# Board_V1_0.net
KiCad netlist of a schematic drawn in Altium Designer
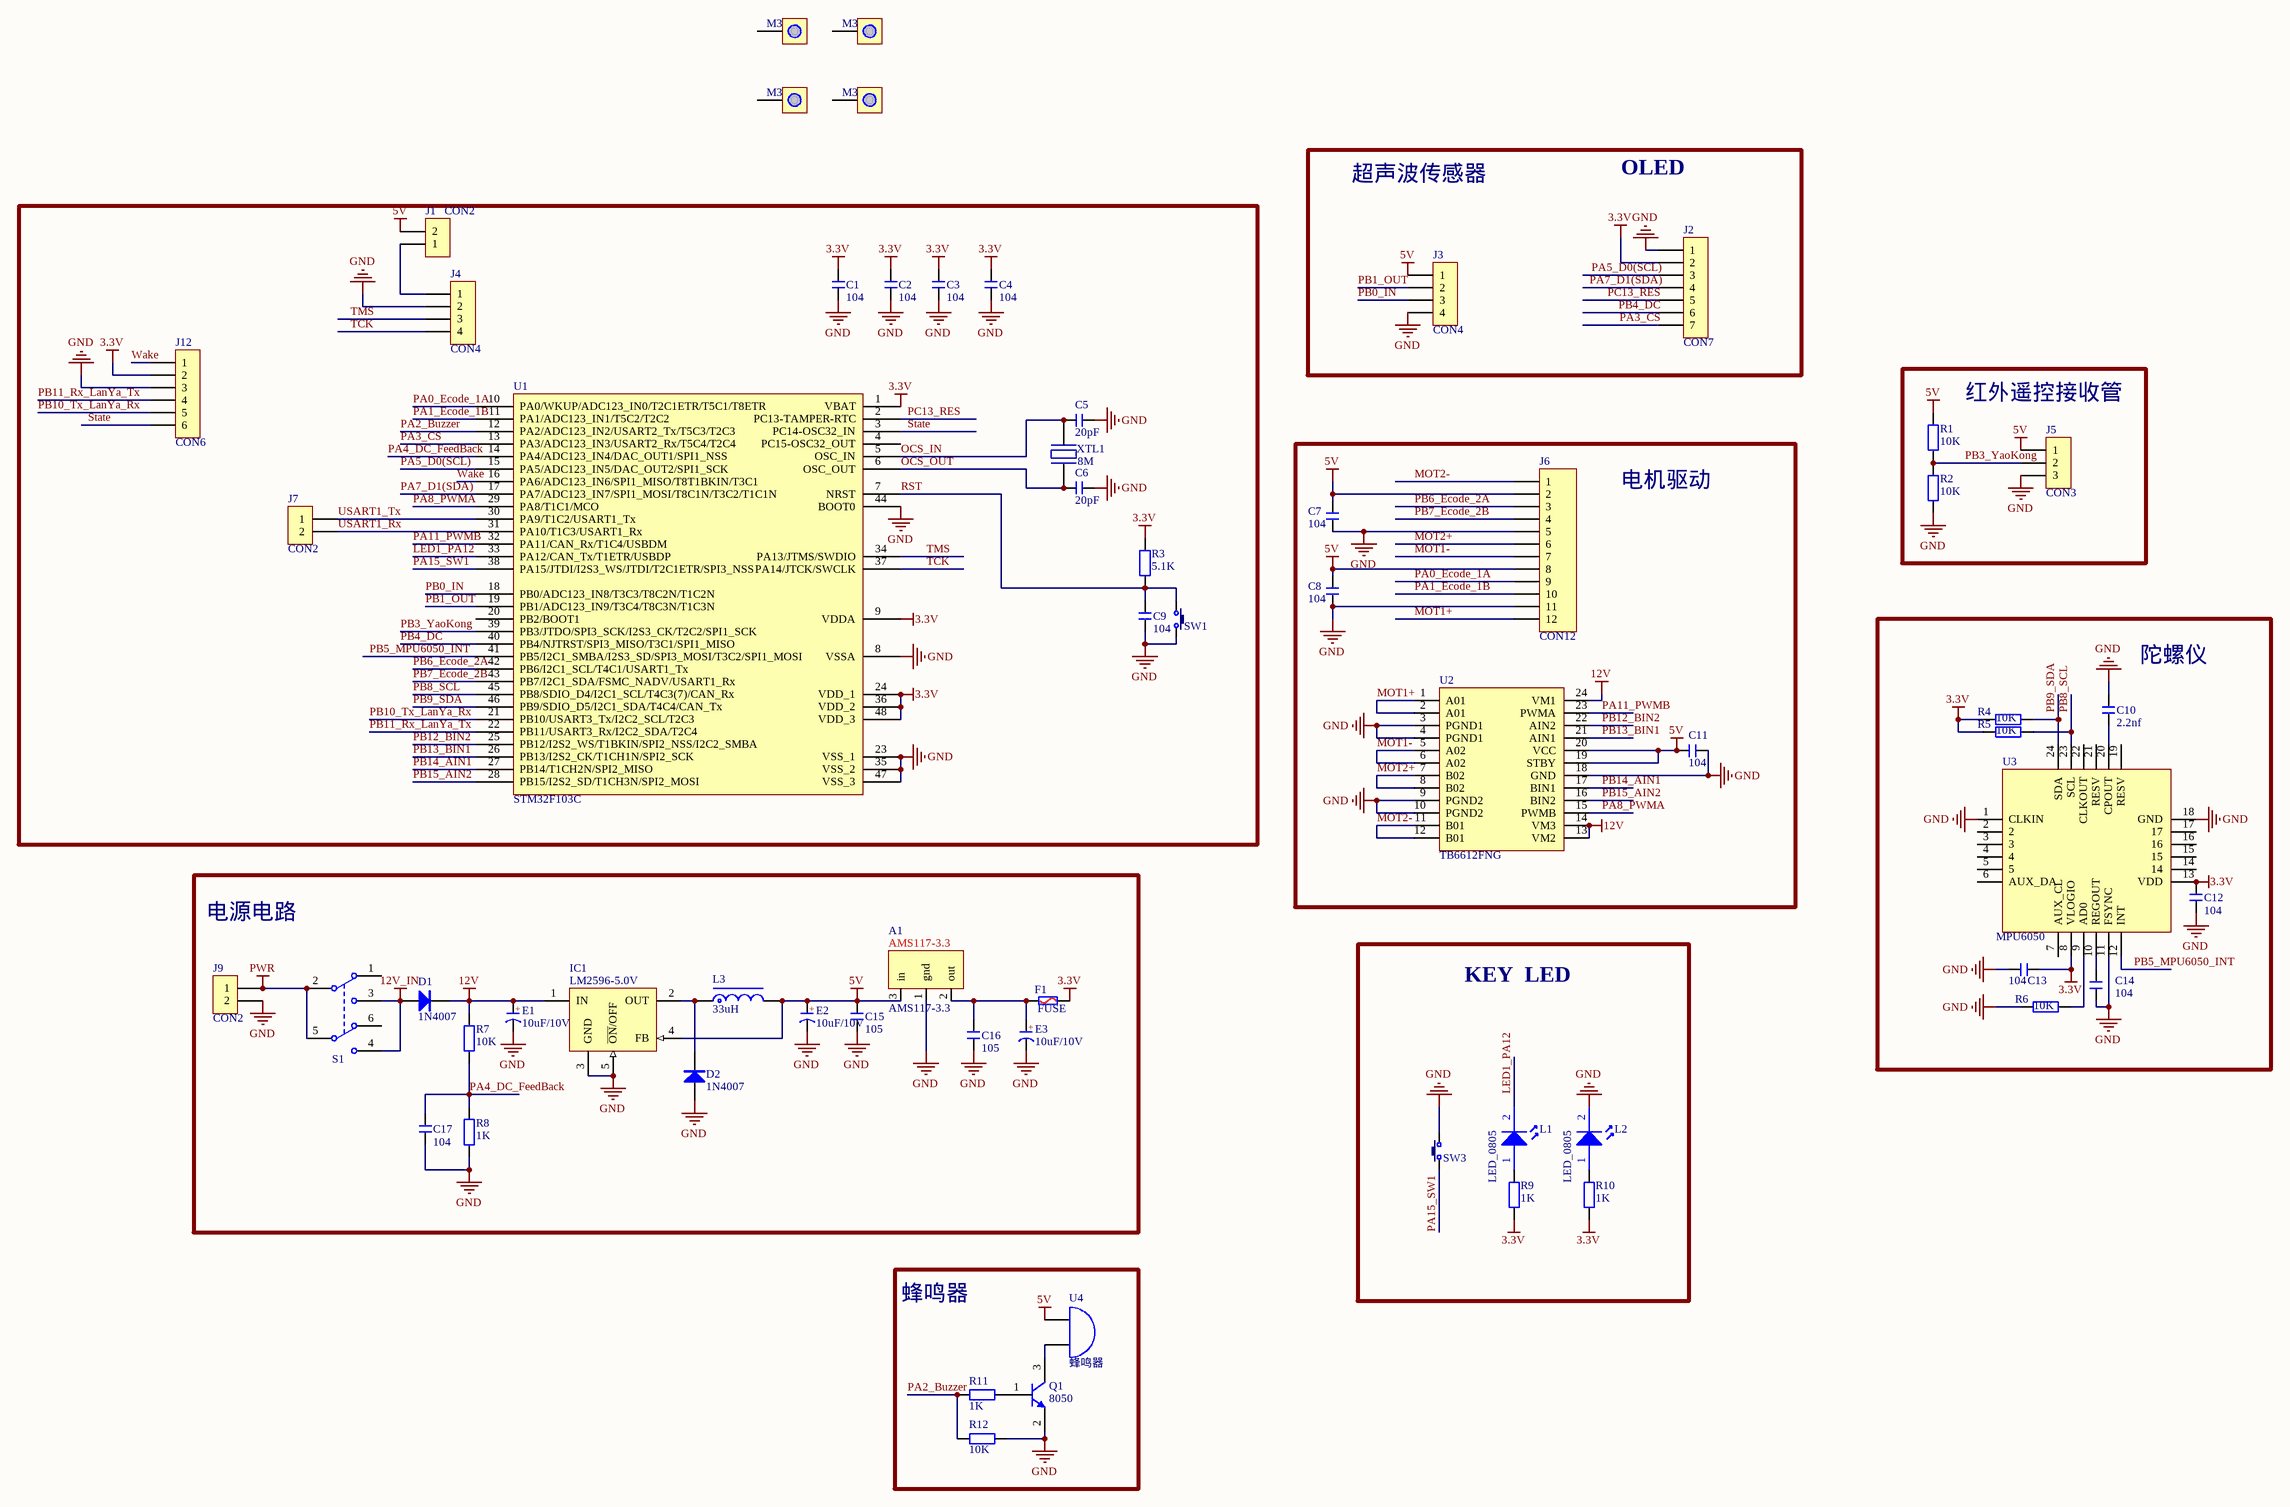
[diagram p0: 平衡车Board_V1.0.SchDoc]

(export (version "E")
  (design (tool "Eeschema 10.0.6"))
  (components
    (comp (ref "A1") (value "AMS117-3.3") (footprint "SOT223_N") (libsource (lib "MP3") (part "AMS117-3.3")))
    (comp (ref "C1")
      (value "104")
      (footprint "C 0603_M")
      (description "无极性贴片电容")
      (libsource (lib "3.1   - 电阻-电容-电感") (part "C"))
    )
    (comp (ref "C2")
      (value "104")
      (footprint "C 0603_M")
      (description "无极性贴片电容")
      (libsource (lib "3.1   - 电阻-电容-电感") (part "C"))
    )
    (comp (ref "C3")
      (value "104")
      (footprint "C 0603_M")
      (description "无极性贴片电容")
      (libsource (lib "3.1   - 电阻-电容-电感") (part "C"))
    )
    (comp (ref "C4")
      (value "104")
      (footprint "C 0603_M")
      (description "无极性贴片电容")
      (libsource (lib "3.1   - 电阻-电容-电感") (part "C"))
    )
    (comp (ref "C5")
      (value "20pF")
      (footprint "C 0603_M")
      (description "无极性贴片电容")
      (libsource (lib "3.1   - 电阻-电容-电感") (part "C"))
    )
    (comp (ref "C6")
      (value "20pF")
      (footprint "C 0603_M")
      (description "无极性贴片电容")
      (libsource (lib "3.1   - 电阻-电容-电感") (part "C"))
    )
    (comp (ref "C7")
      (value "104")
      (footprint "C 0603_M")
      (description "无极性贴片电容")
      (libsource (lib "3.1   - 电阻-电容-电感") (part "C"))
    )
    (comp (ref "C8")
      (value "104")
      (footprint "C 0603_M")
      (description "无极性贴片电容")
      (libsource (lib "3.1   - 电阻-电容-电感") (part "C"))
    )
    (comp (ref "C9")
      (value "104")
      (footprint "C 0603_M")
      (description "无极性贴片电容")
      (libsource (lib "3.1   - 电阻-电容-电感") (part "C"))
    )
    (comp (ref "C10")
      (value "2.2nf")
      (footprint "C 0603_M")
      (description "无极性贴片电容")
      (libsource (lib "3.1   - 电阻-电容-电感") (part "C"))
    )
    (comp (ref "C11")
      (value "104")
      (footprint "C 0603_M")
      (description "无极性贴片电容")
      (libsource (lib "3.1   - 电阻-电容-电感") (part "C"))
    )
    (comp (ref "C12")
      (value "104")
      (footprint "C 0603_M")
      (description "无极性贴片电容")
      (libsource (lib "3.1   - 电阻-电容-电感") (part "C"))
    )
    (comp (ref "C13")
      (value "104")
      (footprint "C 0603_M")
      (description "无极性贴片电容")
      (libsource (lib "3.1   - 电阻-电容-电感") (part "C"))
    )
    (comp (ref "C14")
      (value "104")
      (footprint "C 0603_M")
      (description "无极性贴片电容")
      (libsource (lib "3.1   - 电阻-电容-电感") (part "C"))
    )
    (comp (ref "C15")
      (value "105")
      (footprint "C 0805_M")
      (description "无极性贴片电容")
      (libsource (lib "3.1   - 电阻-电容-电感") (part "C"))
    )
    (comp (ref "C16")
      (value "105")
      (footprint "C 0805_M")
      (description "无极性贴片电容")
      (libsource (lib "3.1   - 电阻-电容-电感") (part "C"))
    )
    (comp (ref "C17")
      (value "104")
      (footprint "C 0603_M")
      (description "无极性贴片电容")
      (libsource (lib "3.1   - 电阻-电容-电感") (part "C"))
    )
    (comp (ref "D1")
      (value "1N4007")
      (footprint "DO-41")
      (description "整流二极管")
      (libsource (lib "8.1   - 二极管-整流桥") (part "1N4007"))
    )
    (comp (ref "D2")
      (value "1N4007")
      (footprint "DO-41")
      (description "整流二极管")
      (libsource (lib "8.1   - 二极管-整流桥") (part "1N4007"))
    )
    (comp (ref "E1")
      (value "10uF/10V")
      (footprint "CM D(6.3*7.7)")
      (description "贴片电解电容")
      (libsource (lib "3.1   - 电阻-电容-电感") (part "C-CM"))
    )
    (comp (ref "E2")
      (value "10uF/10V")
      (footprint "CM D(6.3*7.7)")
      (description "贴片电解电容")
      (libsource (lib "3.1   - 电阻-电容-电感") (part "C-CM"))
    )
    (comp (ref "E3")
      (value "10uF/10V")
      (footprint "CM D(6.3*7.7)")
      (description "贴片电解电容")
      (libsource (lib "3.1   - 电阻-电容-电感") (part "C-CM"))
    )
    (comp (ref "F1") (value "FUSE") (footprint "FU 1206") (libsource (lib "MP3") (part "FUSE")))
    (comp (ref "IC1")
      (value "LM2596-5.0V")
      (footprint "TO263-5A")
      (description "DC降压芯片")
      (libsource (lib "1.3   - 电源类芯片") (part "LM2596-5.0"))
    )
    (comp (ref "J1")
      (value "CON2")
      (footprint "HDR2.54-LI-2P")
      (description "Connector")
      (libsource (lib "") (part "CON2_1"))
    )
    (comp (ref "J2")
      (value "CON7")
      (footprint "HDR2.54-M-LI-7P - for-Oled")
      (description "Connector")
      (libsource (lib "4.16 - 插件") (part "CON7"))
    )
    (comp (ref "J3")
      (value "CON4")
      (footprint "HDR2.54-M-LI-4P")
      (description "Connector")
      (libsource (lib "4.16 - 插件") (part "CON4"))
    )
    (comp (ref "J4")
      (value "CON4")
      (footprint "HDR2.54-WI-4P")
      (description "Connector")
      (libsource (lib "4.16 - 插件") (part "CON4"))
    )
    (comp (ref "J5")
      (value "CON3")
      (footprint "TO92A - duplicate")
      (description "Connector")
      (libsource (lib "4.16 - 插件") (part "CON3"))
    )
    (comp (ref "J6")
      (value "CON12")
      (footprint "XH2.54-LI-12P")
      (description "Connector")
      (libsource (lib "4.16 - 插件") (part "CON12"))
    )
    (comp (ref "J7")
      (value "CON2")
      (footprint "HDR2.54-LI-2P")
      (description "Connector")
      (libsource (lib "4.16 - 插件") (part "CON2"))
    )
    (comp (ref "J9")
      (value "CON2")
      (footprint "CZ-5.08-L-Z-2P")
      (description "Connector")
      (libsource (lib "4.16 - 插件") (part "CON2"))
    )
    (comp (ref "J12")
      (value "CON6")
      (footprint "HDR2.54-M-LI-6P - for-wifi")
      (description "Connector")
      (libsource (lib "4.16 - 插件") (part "CON6"))
    )
    (comp (ref "L1") (value "LED_0805") (footprint "LED 0805G") (libsource (lib "MP3") (part "LED_0805")))
    (comp (ref "L2") (value "LED_0805") (footprint "LED 0805G") (libsource (lib "MP3") (part "LED_0805")))
    (comp (ref "L3")
      (value "33uH")
      (footprint "NR3012")
      (description "NR磁胶电感")
      (libsource (lib "3.1   - 电阻-电容-电感") (part "L-NR"))
    )
    (comp (ref "M3") (value "M3") (footprint "M3x20_L") (libsource (lib "MP3") (part "M3")))
    (comp (ref "M4") (value "M3") (footprint "M3x20_L") (libsource (lib "MP3") (part "M3")))
    (comp (ref "M5") (value "M3") (footprint "M3x20_L") (libsource (lib "MP3") (part "M3")))
    (comp (ref "M6") (value "M3") (footprint "M3x20_L") (libsource (lib "MP3") (part "M3")))
    (comp (ref "Q1") (value "8050") (footprint "SOT23-3M") (libsource (lib "PCB_M") (part "NPN")))
    (comp (ref "R1")
      (value "10K")
      (footprint "R 0603_M")
      (description "贴片电阻")
      (libsource (lib "3.1   - 电阻-电容-电感") (part "R"))
    )
    (comp (ref "R2")
      (value "10K")
      (footprint "R 0603_M")
      (description "贴片电阻")
      (libsource (lib "3.1   - 电阻-电容-电感") (part "R"))
    )
    (comp (ref "R3")
      (value "5.1K")
      (footprint "R 0603_M")
      (description "贴片电阻")
      (libsource (lib "3.1   - 电阻-电容-电感") (part "R"))
    )
    (comp (ref "R4")
      (value "10K")
      (footprint "R 0603_M")
      (description "贴片电阻")
      (libsource (lib "3.1   - 电阻-电容-电感") (part "R"))
    )
    (comp (ref "R5")
      (value "10K")
      (footprint "R 0603_M")
      (description "贴片电阻")
      (libsource (lib "3.1   - 电阻-电容-电感") (part "R"))
    )
    (comp (ref "R6")
      (value "10K")
      (footprint "R 0603_M")
      (description "贴片电阻")
      (libsource (lib "3.1   - 电阻-电容-电感") (part "R"))
    )
    (comp (ref "R7")
      (value "10K")
      (footprint "R 0603_M")
      (description "贴片电阻")
      (libsource (lib "3.1   - 电阻-电容-电感") (part "R"))
    )
    (comp (ref "R8")
      (value "1K")
      (footprint "R 0603_M")
      (description "贴片电阻")
      (libsource (lib "3.1   - 电阻-电容-电感") (part "R"))
    )
    (comp (ref "R9")
      (value "1K")
      (footprint "R 0603_M")
      (description "贴片电阻")
      (libsource (lib "3.1   - 电阻-电容-电感") (part "R"))
    )
    (comp (ref "R10")
      (value "1K")
      (footprint "R 0603_M")
      (description "贴片电阻")
      (libsource (lib "3.1   - 电阻-电容-电感") (part "R"))
    )
    (comp (ref "R11")
      (value "1K")
      (footprint "R 0603_M")
      (description "贴片电阻")
      (libsource (lib "3.1   - 电阻-电容-电感") (part "R"))
    )
    (comp (ref "R12")
      (value "10K")
      (footprint "R 0603_M")
      (description "贴片电阻")
      (libsource (lib "3.1   - 电阻-电容-电感") (part "R"))
    )
    (comp (ref "S1")
      (value "SK-22D02")
      (footprint "SK-22D02")
      (description "2路波动开关")
      (libsource (lib "5.1   - 按键-开关") (part "SSW-2P"))
    )
    (comp (ref "SW1")
      (value "3x6x5")
      (footprint "TSW DIP-6*6*5")
      (description "3x6轻触开关")
      (libsource (lib "5.1   - 按键-开关") (part "TSW 3x6"))
    )
    (comp (ref "SW3")
      (value "3x6x5")
      (footprint "TSW DIP-6*6*5")
      (description "3x6轻触开关")
      (libsource (lib "") (part "TSW 3x6_1"))
    )
    (comp (ref "U1")
      (value "STM32F103C")
      (footprint "LQFP48 7X7_M")
      (description "STM32单片机48引脚")
      (libsource (lib "2.3.8 - STM32芯片") (part "STM32F103C"))
    )
    (comp (ref "U2")
      (value "TB6612FNG")
      (footprint "SSOP24_M")
      (description "直流电机驱动芯片")
      (libsource (lib "MP3") (part "TB6612FNG"))
    )
    (comp (ref "U3")
      (value "MPU6050")
      (footprint "QFN24 4x4_M")
      (description "陀螺仪")
      (libsource (lib "MP3") (part "MPU6050"))
    )
    (comp (ref "U4")
      (value "蜂鸣器")
      (footprint "BEEP 5x9x5.5")
      (description "Bell")
      (libsource (lib "9.2.1 - 声亮元件") (part "蜂鸣器"))
    )
    (comp (ref "XTL1") (value "8M") (footprint "OSC HC-49S") (libsource (lib "MP3") (part "XTL")))
  )
  (nets
    (net (code "1") (name "/LED1_PA12") (class "Default")
      (node (ref "L1") (pin "2") (pinfunction "2_2") (pintype "passive"))
      (node (ref "U1") (pin "33") (pinfunction "PA12/CAN_Tx/T1ETR/USBDP_33") (pintype "passive"))
    )
    (net (code "2") (name "/MOT1+") (class "Default")
      (node (ref "J6") (pin "12") (pinfunction "12_12") (pintype "passive"))
      (node (ref "U2") (pin "1") (pinfunction "A01_1") (pintype "passive"))
      (node (ref "U2") (pin "2") (pinfunction "A01_2") (pintype "passive"))
    )
    (net (code "3") (name "/MOT1-") (class "Default")
      (node (ref "J6") (pin "7") (pinfunction "7_7") (pintype "passive"))
      (node (ref "U2") (pin "5") (pinfunction "A02_5") (pintype "passive"))
      (node (ref "U2") (pin "6") (pinfunction "A02_6") (pintype "passive"))
    )
    (net (code "4") (name "/MOT2+") (class "Default")
      (node (ref "J6") (pin "6") (pinfunction "6_6") (pintype "passive"))
      (node (ref "U2") (pin "7") (pinfunction "B02_7") (pintype "passive"))
      (node (ref "U2") (pin "8") (pinfunction "B02_8") (pintype "passive"))
    )
    (net (code "5") (name "/MOT2-") (class "Default")
      (node (ref "J6") (pin "1") (pinfunction "1_1") (pintype "passive"))
      (node (ref "U2") (pin "11") (pinfunction "B01_11") (pintype "passive"))
      (node (ref "U2") (pin "12") (pinfunction "B01_12") (pintype "passive"))
    )
    (net (code "6") (name "/OCS_IN") (class "Default")
      (node (ref "C5") (pin "2") (pinfunction "2_2") (pintype "passive"))
      (node (ref "U1") (pin "5") (pinfunction "OSC_IN_5") (pintype "passive"))
      (node (ref "XTL1") (pin "2") (pinfunction "2_2") (pintype "passive"))
    )
    (net (code "7") (name "/OCS_OUT") (class "Default")
      (node (ref "C6") (pin "2") (pinfunction "2_2") (pintype "passive"))
      (node (ref "U1") (pin "6") (pinfunction "OSC_OUT_6") (pintype "passive"))
      (node (ref "XTL1") (pin "1") (pinfunction "1_1") (pintype "passive"))
    )
    (net (code "8") (name "/PA0_Ecode_1A") (class "Default")
      (node (ref "J6") (pin "9") (pinfunction "9_9") (pintype "passive"))
      (node (ref "U1") (pin "10") (pinfunction "PA0/WKUP/ADC123_IN0/T2C1ETR/T5C1/T8ETR_10") (pintype "passive"))
    )
    (net (code "9") (name "/PA1_Ecode_1B") (class "Default")
      (node (ref "J6") (pin "10") (pinfunction "10_10") (pintype "passive"))
      (node (ref "U1") (pin "11") (pinfunction "PA1/ADC123_IN1/T5C2/T2C2_11") (pintype "passive"))
    )
    (net (code "10") (name "/PA2_Buzzer") (class "Default")
      (node (ref "R11") (pin "2") (pinfunction "2_2") (pintype "passive"))
      (node (ref "R12") (pin "2") (pinfunction "2_2") (pintype "passive"))
      (node (ref "U1") (pin "12") (pinfunction "PA2/ADC123_IN2/USART2_Tx/T5C3/T2C3_12") (pintype "passive"))
    )
    (net (code "11") (name "/PA3_CS") (class "Default")
      (node (ref "J2") (pin "7") (pinfunction "7_7") (pintype "passive"))
      (node (ref "U1") (pin "13") (pinfunction "PA3/ADC123_IN3/USART2_Rx/T5C4/T2C4_13") (pintype "passive"))
    )
    (net (code "12") (name "/PA4_DC_FeedBack") (class "Default")
      (node (ref "C17") (pin "2") (pinfunction "2_2") (pintype "passive"))
      (node (ref "R7") (pin "1") (pinfunction "1_1") (pintype "passive"))
      (node (ref "R8") (pin "2") (pinfunction "2_2") (pintype "passive"))
      (node (ref "U1") (pin "14") (pinfunction "PA4/ADC123_IN4/DAC_OUT1/SPI1_NSS_14") (pintype "passive"))
    )
    (net (code "13") (name "/PA5_D0(SCL)") (class "Default")
      (node (ref "J2") (pin "3") (pinfunction "3_3") (pintype "passive"))
      (node (ref "U1") (pin "15") (pinfunction "PA5/ADC123_IN5/DAC_OUT2/SPI1_SCK_15") (pintype "passive"))
    )
    (net (code "14") (name "/PA7_D1(SDA)") (class "Default")
      (node (ref "J2") (pin "4") (pinfunction "4_4") (pintype "passive"))
      (node (ref "U1") (pin "17") (pinfunction "PA7/ADC123_IN7/SPI1_MOSI/T8C1N/T3C2/T1C1N_17") (pintype "passive"))
    )
    (net (code "15") (name "/PA8_PWMA") (class "Default")
      (node (ref "U1") (pin "29") (pinfunction "PA8/T1C1/MCO_29") (pintype "passive"))
      (node (ref "U2") (pin "15") (pinfunction "PWMB_15") (pintype "passive"))
    )
    (net (code "16") (name "/PA11_PWMB") (class "Default")
      (node (ref "U1") (pin "32") (pinfunction "PA11/CAN_Rx/T1C4/USBDM_32") (pintype "passive"))
      (node (ref "U2") (pin "23") (pinfunction "PWMA_23") (pintype "passive"))
    )
    (net (code "17") (name "/PA15_SW1") (class "Default")
      (node (ref "SW3") (pin "1") (pinfunction "1_1") (pintype "passive"))
      (node (ref "U1") (pin "38") (pinfunction "PA15/JTDI/I2S3_WS/JTDI/T2C1ETR/SPI3_NSS_38") (pintype "passive"))
    )
    (net (code "18") (name "/PB0_IN") (class "Default")
      (node (ref "J3") (pin "3") (pinfunction "3_3") (pintype "passive"))
      (node (ref "U1") (pin "18") (pinfunction "PB0/ADC123_IN8/T3C3/T8C2N/T1C2N_18") (pintype "passive"))
    )
    (net (code "19") (name "/PB1_OUT") (class "Default")
      (node (ref "J3") (pin "2") (pinfunction "2_2") (pintype "passive"))
      (node (ref "U1") (pin "19") (pinfunction "PB1/ADC123_IN9/T3C4/T8C3N/T1C3N_19") (pintype "passive"))
    )
    (net (code "20") (name "/PB3_YaoKong") (class "Default")
      (node (ref "J5") (pin "2") (pinfunction "2_2") (pintype "passive"))
      (node (ref "R1") (pin "1") (pinfunction "1_1") (pintype "passive"))
      (node (ref "R2") (pin "1") (pinfunction "1_1") (pintype "passive"))
      (node (ref "U1") (pin "39") (pinfunction "PB3/JTDO/SPI3_SCK/I2S3_CK/T2C2/SPI1_SCK_39") (pintype "passive"))
    )
    (net (code "21") (name "/PB4_DC") (class "Default")
      (node (ref "J2") (pin "6") (pinfunction "6_6") (pintype "passive"))
      (node (ref "U1") (pin "40") (pinfunction "PB4/NJTRST/SPI3_MISO/T3C1/SPI1_MISO_40") (pintype "passive"))
    )
    (net (code "22") (name "/PB5_MPU6050_INT") (class "Default")
      (node (ref "U1") (pin "41") (pinfunction "PB5/I2C1_SMBA/I2S3_SD/SPI3_MOSI/T3C2/SPI1_MOSI_41") (pintype "passive"))
      (node (ref "U3") (pin "12") (pinfunction "INT_12") (pintype "passive"))
    )
    (net (code "23") (name "/PB6_Ecode_2A") (class "Default")
      (node (ref "J6") (pin "3") (pinfunction "3_3") (pintype "passive"))
      (node (ref "U1") (pin "42") (pinfunction "PB6/I2C1_SCL/T4C1/USART1_Tx_42") (pintype "passive"))
    )
    (net (code "24") (name "/PB7_Ecode_2B") (class "Default")
      (node (ref "J6") (pin "4") (pinfunction "4_4") (pintype "passive"))
      (node (ref "U1") (pin "43") (pinfunction "PB7/I2C1_SDA/FSMC_NADV/USART1_Rx_43") (pintype "passive"))
    )
    (net (code "25") (name "/PB8_SCL") (class "Default")
      (node (ref "R5") (pin "1") (pinfunction "1_1") (pintype "passive"))
      (node (ref "U1") (pin "45") (pinfunction "PB8/SDIO_D4/I2C1_SCL/T4C3(7)/CAN_Rx_45") (pintype "passive"))
      (node (ref "U3") (pin "23") (pinfunction "SCL_23") (pintype "passive"))
    )
    (net (code "26") (name "/PB9_SDA") (class "Default")
      (node (ref "R4") (pin "1") (pinfunction "1_1") (pintype "passive"))
      (node (ref "U1") (pin "46") (pinfunction "PB9/SDIO_D5/I2C1_SDA/T4C4/CAN_Tx_46") (pintype "passive"))
      (node (ref "U3") (pin "24") (pinfunction "SDA_24") (pintype "passive"))
    )
    (net (code "27") (name "/PB10_Tx_LanYa_Rx") (class "Default")
      (node (ref "J12") (pin "5") (pinfunction "5_5") (pintype "passive"))
      (node (ref "U1") (pin "21") (pinfunction "PB10/USART3_Tx/I2C2_SCL/T2C3_21") (pintype "passive"))
    )
    (net (code "28") (name "/PB11_Rx_LanYa_Tx") (class "Default")
      (node (ref "J12") (pin "4") (pinfunction "4_4") (pintype "passive"))
      (node (ref "U1") (pin "22") (pinfunction "PB11/USART3_Rx/I2C2_SDA/T2C4_22") (pintype "passive"))
    )
    (net (code "29") (name "/PB12_BIN2") (class "Default")
      (node (ref "U1") (pin "25") (pinfunction "PB12/I2S2_WS/T1BKIN/SPI2_NSS/I2C2_SMBA_25") (pintype "passive"))
      (node (ref "U2") (pin "22") (pinfunction "AIN2_22") (pintype "passive"))
    )
    (net (code "30") (name "/PB13_BIN1") (class "Default")
      (node (ref "U1") (pin "26") (pinfunction "PB13/I2S2_CK/T1CH1N/SPI2_SCK_26") (pintype "passive"))
      (node (ref "U2") (pin "21") (pinfunction "AIN1_21") (pintype "passive"))
    )
    (net (code "31") (name "/PB14_AIN1") (class "Default")
      (node (ref "U1") (pin "27") (pinfunction "PB14/T1CH2N/SPI2_MISO_27") (pintype "passive"))
      (node (ref "U2") (pin "17") (pinfunction "BIN1_17") (pintype "passive"))
    )
    (net (code "32") (name "/PB15_AIN2") (class "Default")
      (node (ref "U1") (pin "28") (pinfunction "PB15/I2S2_SD/T1CH3N/SPI2_MOSI_28") (pintype "passive"))
      (node (ref "U2") (pin "16") (pinfunction "BIN2_16") (pintype "passive"))
    )
    (net (code "33") (name "/PC13_RES") (class "Default")
      (node (ref "J2") (pin "5") (pinfunction "5_5") (pintype "passive"))
      (node (ref "U1") (pin "2") (pinfunction "PC13-TAMPER-RTC_2") (pintype "passive"))
    )
    (net (code "34") (name "/RST") (class "Default")
      (node (ref "C9") (pin "2") (pinfunction "2_2") (pintype "passive"))
      (node (ref "R3") (pin "1") (pinfunction "1_1") (pintype "passive"))
      (node (ref "SW1") (pin "1") (pinfunction "1_1") (pintype "passive"))
      (node (ref "U1") (pin "7") (pinfunction "NRST_7") (pintype "passive"))
    )
    (net (code "35") (name "/State") (class "Default")
      (node (ref "J12") (pin "6") (pinfunction "6_6") (pintype "passive"))
      (node (ref "U1") (pin "3") (pinfunction "PC14-OSC32_IN_3") (pintype "passive"))
    )
    (net (code "36") (name "/TCK") (class "Default")
      (node (ref "J4") (pin "4") (pinfunction "4_4") (pintype "passive"))
      (node (ref "U1") (pin "37") (pinfunction "PA14/JTCK/SWCLK_37") (pintype "passive"))
    )
    (net (code "37") (name "/TMS") (class "Default")
      (node (ref "J4") (pin "3") (pinfunction "3_3") (pintype "passive"))
      (node (ref "U1") (pin "34") (pinfunction "PA13/JTMS/SWDIO_34") (pintype "passive"))
    )
    (net (code "38") (name "/USART1_Rx") (class "Default")
      (node (ref "J7") (pin "2") (pinfunction "2_2") (pintype "passive"))
      (node (ref "U1") (pin "31") (pinfunction "PA10/T1C3/USART1_Rx_31") (pintype "passive"))
    )
    (net (code "39") (name "/USART1_Tx") (class "Default")
      (node (ref "J7") (pin "1") (pinfunction "1_1") (pintype "passive"))
      (node (ref "U1") (pin "30") (pinfunction "PA9/T1C2/USART1_Tx_30") (pintype "passive"))
    )
    (net (code "40") (name "/Wake") (class "Default")
      (node (ref "J12") (pin "1") (pinfunction "1_1") (pintype "passive"))
      (node (ref "U1") (pin "16") (pinfunction "PA6/ADC123_IN6/SPI1_MISO/T8T1BKIN/T3C1_16") (pintype "passive"))
    )
    (net (code "41") (name "3.3V") (class "Default")
      (node (ref "C1") (pin "2") (pinfunction "2_2") (pintype "passive"))
      (node (ref "C12") (pin "2") (pinfunction "2_2") (pintype "passive"))
      (node (ref "C13") (pin "1") (pinfunction "1_1") (pintype "passive"))
      (node (ref "C2") (pin "2") (pinfunction "2_2") (pintype "passive"))
      (node (ref "C3") (pin "2") (pinfunction "2_2") (pintype "passive"))
      (node (ref "C4") (pin "2") (pinfunction "2_2") (pintype "passive"))
      (node (ref "F1") (pin "1") (pinfunction "1_1") (pintype "passive"))
      (node (ref "J12") (pin "2") (pinfunction "2_2") (pintype "passive"))
      (node (ref "J2") (pin "2") (pinfunction "2_2") (pintype "passive"))
      (node (ref "R10") (pin "1") (pinfunction "1_1") (pintype "passive"))
      (node (ref "R3") (pin "2") (pinfunction "2_2") (pintype "passive"))
      (node (ref "R4") (pin "2") (pinfunction "2_2") (pintype "passive"))
      (node (ref "R5") (pin "2") (pinfunction "2_2") (pintype "passive"))
      (node (ref "R9") (pin "1") (pinfunction "1_1") (pintype "passive"))
      (node (ref "U1") (pin "1") (pinfunction "VBAT_1") (pintype "passive"))
      (node (ref "U1") (pin "24") (pinfunction "VDD_1_24") (pintype "passive"))
      (node (ref "U1") (pin "36") (pinfunction "VDD_2_36") (pintype "passive"))
      (node (ref "U1") (pin "48") (pinfunction "VDD_3_48") (pintype "passive"))
      (node (ref "U1") (pin "9") (pinfunction "VDDA_9") (pintype "passive"))
      (node (ref "U3") (pin "13") (pinfunction "VDD_13") (pintype "passive"))
      (node (ref "U3") (pin "8") (pinfunction "VLOGIO_8") (pintype "passive"))
    )
    (net (code "42") (name "5V") (class "Default")
      (node (ref "A1") (pin "3") (pinfunction "in_3") (pintype "passive"))
      (node (ref "C11") (pin "2") (pinfunction "2_2") (pintype "passive"))
      (node (ref "C15") (pin "2") (pinfunction "2_2") (pintype "passive"))
      (node (ref "C7") (pin "2") (pinfunction "2_2") (pintype "passive"))
      (node (ref "C8") (pin "2") (pinfunction "2_2") (pintype "passive"))
      (node (ref "E2") (pin "1") (pinfunction "A_1") (pintype "passive"))
      (node (ref "IC1") (pin "4") (pinfunction "FB_4") (pintype "input"))
      (node (ref "J1") (pin "2") (pinfunction "2_2") (pintype "passive"))
      (node (ref "J3") (pin "1") (pinfunction "1_1") (pintype "passive"))
      (node (ref "J5") (pin "1") (pinfunction "1_1") (pintype "passive"))
      (node (ref "J6") (pin "2") (pinfunction "2_2") (pintype "passive"))
      (node (ref "J6") (pin "8") (pinfunction "8_8") (pintype "passive"))
      (node (ref "L3") (pin "2") (pinfunction "2_2") (pintype "passive"))
      (node (ref "R1") (pin "2") (pinfunction "2_2") (pintype "passive"))
      (node (ref "U2") (pin "19") (pinfunction "STBY_19") (pintype "passive"))
      (node (ref "U2") (pin "20") (pinfunction "VCC_20") (pintype "passive"))
      (node (ref "U4") (pin "1") (pinfunction "A_1") (pintype "passive"))
    )
    (net (code "43") (name "12V") (class "Default")
      (node (ref "D1") (pin "2") (pinfunction "K_2") (pintype "passive"))
      (node (ref "E1") (pin "1") (pinfunction "A_1") (pintype "passive"))
      (node (ref "IC1") (pin "1") (pinfunction "IN_1") (pintype "power_in"))
      (node (ref "R7") (pin "2") (pinfunction "2_2") (pintype "passive"))
      (node (ref "U2") (pin "13") (pinfunction "VM2_13") (pintype "passive"))
      (node (ref "U2") (pin "14") (pinfunction "VM3_14") (pintype "passive"))
      (node (ref "U2") (pin "24") (pinfunction "VM1_24") (pintype "passive"))
    )
    (net (code "44") (name "12V_IN") (class "Default")
      (node (ref "D1") (pin "1") (pinfunction "A_1") (pintype "passive"))
      (node (ref "S1") (pin "3") (pinfunction "3_3") (pintype "passive"))
      (node (ref "S1") (pin "4") (pinfunction "4_4") (pintype "passive"))
    )
    (net (code "45") (name "GND") (class "Default")
      (node (ref "A1") (pin "1") (pinfunction "gnd_1") (pintype "passive"))
      (node (ref "C1") (pin "1") (pinfunction "1_1") (pintype "passive"))
      (node (ref "C10") (pin "2") (pinfunction "2_2") (pintype "passive"))
      (node (ref "C11") (pin "1") (pinfunction "1_1") (pintype "passive"))
      (node (ref "C12") (pin "1") (pinfunction "1_1") (pintype "passive"))
      (node (ref "C13") (pin "2") (pinfunction "2_2") (pintype "passive"))
      (node (ref "C14") (pin "1") (pinfunction "1_1") (pintype "passive"))
      (node (ref "C15") (pin "1") (pinfunction "1_1") (pintype "passive"))
      (node (ref "C16") (pin "1") (pinfunction "1_1") (pintype "passive"))
      (node (ref "C17") (pin "1") (pinfunction "1_1") (pintype "passive"))
      (node (ref "C2") (pin "1") (pinfunction "1_1") (pintype "passive"))
      (node (ref "C3") (pin "1") (pinfunction "1_1") (pintype "passive"))
      (node (ref "C4") (pin "1") (pinfunction "1_1") (pintype "passive"))
      (node (ref "C5") (pin "1") (pinfunction "1_1") (pintype "passive"))
      (node (ref "C6") (pin "1") (pinfunction "1_1") (pintype "passive"))
      (node (ref "C7") (pin "1") (pinfunction "1_1") (pintype "passive"))
      (node (ref "C8") (pin "1") (pinfunction "1_1") (pintype "passive"))
      (node (ref "C9") (pin "1") (pinfunction "1_1") (pintype "passive"))
      (node (ref "D2") (pin "1") (pinfunction "A_1") (pintype "passive"))
      (node (ref "E1") (pin "2") (pinfunction "K_2") (pintype "passive"))
      (node (ref "E2") (pin "2") (pinfunction "K_2") (pintype "passive"))
      (node (ref "E3") (pin "2") (pinfunction "K_2") (pintype "passive"))
      (node (ref "IC1") (pin "3") (pinfunction "GND_3") (pintype "power_in"))
      (node (ref "IC1") (pin "5") (pinfunction "~{ON}/OFF_5") (pintype "input"))
      (node (ref "J12") (pin "3") (pinfunction "3_3") (pintype "passive"))
      (node (ref "J2") (pin "1") (pinfunction "1_1") (pintype "passive"))
      (node (ref "J3") (pin "4") (pinfunction "4_4") (pintype "passive"))
      (node (ref "J4") (pin "2") (pinfunction "2_2") (pintype "passive"))
      (node (ref "J5") (pin "3") (pinfunction "3_3") (pintype "passive"))
      (node (ref "J6") (pin "11") (pinfunction "11_11") (pintype "passive"))
      (node (ref "J6") (pin "5") (pinfunction "5_5") (pintype "passive"))
      (node (ref "J9") (pin "2") (pinfunction "2_2") (pintype "passive"))
      (node (ref "L2") (pin "2") (pinfunction "2_2") (pintype "passive"))
      (node (ref "Q1") (pin "2") (pinfunction "E_2") (pintype "passive"))
      (node (ref "R12") (pin "1") (pinfunction "1_1") (pintype "passive"))
      (node (ref "R2") (pin "2") (pinfunction "2_2") (pintype "passive"))
      (node (ref "R6") (pin "2") (pinfunction "2_2") (pintype "passive"))
      (node (ref "R8") (pin "1") (pinfunction "1_1") (pintype "passive"))
      (node (ref "SW1") (pin "2") (pinfunction "2_2") (pintype "passive"))
      (node (ref "SW3") (pin "2") (pinfunction "2_2") (pintype "passive"))
      (node (ref "U1") (pin "23") (pinfunction "VSS_1_23") (pintype "passive"))
      (node (ref "U1") (pin "35") (pinfunction "VSS_2_35") (pintype "passive"))
      (node (ref "U1") (pin "44") (pinfunction "BOOT0_44") (pintype "passive"))
      (node (ref "U1") (pin "47") (pinfunction "VSS_3_47") (pintype "passive"))
      (node (ref "U1") (pin "8") (pinfunction "VSSA_8") (pintype "passive"))
      (node (ref "U2") (pin "10") (pinfunction "PGND2_10") (pintype "passive"))
      (node (ref "U2") (pin "18") (pinfunction "GND_18") (pintype "passive"))
      (node (ref "U2") (pin "3") (pinfunction "PGND1_3") (pintype "passive"))
      (node (ref "U2") (pin "4") (pinfunction "PGND1_4") (pintype "passive"))
      (node (ref "U2") (pin "9") (pinfunction "PGND2_9") (pintype "passive"))
      (node (ref "U3") (pin "1") (pinfunction "CLKIN_1") (pintype "passive"))
      (node (ref "U3") (pin "11") (pinfunction "FSYNC_11") (pintype "passive"))
      (node (ref "U3") (pin "18") (pinfunction "GND_18") (pintype "passive"))
    )
    (net (code "46") (name "Net-(A1-out)") (class "Default")
      (node (ref "A1") (pin "2") (pinfunction "out_2") (pintype "passive"))
      (node (ref "C16") (pin "2") (pinfunction "2_2") (pintype "passive"))
      (node (ref "E3") (pin "1") (pinfunction "A_1") (pintype "passive"))
      (node (ref "F1") (pin "2") (pinfunction "2_2") (pintype "passive"))
    )
    (net (code "47") (name "Net-(D2-K)") (class "Default")
      (node (ref "D2") (pin "2") (pinfunction "K_2") (pintype "passive"))
      (node (ref "IC1") (pin "2") (pinfunction "OUT_2") (pintype "power_in"))
      (node (ref "L3") (pin "1") (pinfunction "1_1") (pintype "passive"))
    )
    (net (code "48") (name "Net-(J1-Pad1)") (class "Default")
      (node (ref "J1") (pin "1") (pinfunction "1_1") (pintype "passive"))
      (node (ref "J4") (pin "1") (pinfunction "1_1") (pintype "passive"))
    )
    (net (code "49") (name "Net-(L1-Pad1)") (class "Default")
      (node (ref "L1") (pin "1") (pinfunction "1_1") (pintype "passive"))
      (node (ref "R9") (pin "2") (pinfunction "2_2") (pintype "passive"))
    )
    (net (code "50") (name "Net-(L2-Pad1)") (class "Default")
      (node (ref "L2") (pin "1") (pinfunction "1_1") (pintype "passive"))
      (node (ref "R10") (pin "2") (pinfunction "2_2") (pintype "passive"))
    )
    (net (code "51") (name "Net-(Q1-B)") (class "Default")
      (node (ref "Q1") (pin "1") (pinfunction "B_1") (pintype "passive"))
      (node (ref "R11") (pin "1") (pinfunction "1_1") (pintype "passive"))
    )
    (net (code "52") (name "Net-(Q1-C)") (class "Default")
      (node (ref "Q1") (pin "3") (pinfunction "C_3") (pintype "passive"))
      (node (ref "U4") (pin "2") (pinfunction "B_2") (pintype "passive"))
    )
    (net (code "53") (name "Net-(U3-AD0)") (class "Default")
      (node (ref "R6") (pin "1") (pinfunction "1_1") (pintype "passive"))
      (node (ref "U3") (pin "9") (pinfunction "AD0_9") (pintype "passive"))
    )
    (net (code "54") (name "Net-(U3-CPOUT)") (class "Default")
      (node (ref "C10") (pin "1") (pinfunction "1_1") (pintype "passive"))
      (node (ref "U3") (pin "20") (pinfunction "CPOUT_20") (pintype "passive"))
    )
    (net (code "55") (name "Net-(U3-REGOUT)") (class "Default")
      (node (ref "C14") (pin "2") (pinfunction "2_2") (pintype "passive"))
      (node (ref "U3") (pin "10") (pinfunction "REGOUT_10") (pintype "passive"))
    )
    (net (code "56") (name "PWR") (class "Default")
      (node (ref "J9") (pin "1") (pinfunction "1_1") (pintype "passive"))
      (node (ref "S1") (pin "2") (pinfunction "2_2") (pintype "passive"))
      (node (ref "S1") (pin "5") (pinfunction "5_5") (pintype "passive"))
    )
    (net (code "57") (name "unconnected-(M3-A-Pad1)") (class "Default")
      (node (ref "M3") (pin "1") (pinfunction "A_1") (pintype "passive"))
    )
    (net (code "58") (name "unconnected-(M4-A-Pad1)") (class "Default")
      (node (ref "M4") (pin "1") (pinfunction "A_1") (pintype "passive"))
    )
    (net (code "59") (name "unconnected-(M5-A-Pad1)") (class "Default")
      (node (ref "M5") (pin "1") (pinfunction "A_1") (pintype "passive"))
    )
    (net (code "60") (name "unconnected-(M6-A-Pad1)") (class "Default")
      (node (ref "M6") (pin "1") (pinfunction "A_1") (pintype "passive"))
    )
    (net (code "61") (name "unconnected-(S1-Pad1)") (class "Default")
      (node (ref "S1") (pin "1") (pinfunction "1_1") (pintype "passive"))
    )
    (net (code "62") (name "unconnected-(S1-Pad6)") (class "Default")
      (node (ref "S1") (pin "6") (pinfunction "6_6") (pintype "passive"))
    )
    (net (code "63") (name "unconnected-(U1-PB2{slash}BOOT1-Pad20)") (class "Default")
      (node (ref "U1") (pin "20") (pinfunction "PB2/BOOT1_20") (pintype "passive"))
    )
    (net (code "64") (name "unconnected-(U1-PC15-OSC32_OUT-Pad4)") (class "Default")
      (node (ref "U1") (pin "4") (pinfunction "PC15-OSC32_OUT_4") (pintype "passive"))
    )
    (net (code "65") (name "unconnected-(U3-AUX_CL-Pad7)") (class "Default")
      (node (ref "U3") (pin "7") (pinfunction "AUX_CL_7") (pintype "passive"))
    )
    (net (code "66") (name "unconnected-(U3-AUX_DA-Pad6)") (class "Default")
      (node (ref "U3") (pin "6") (pinfunction "AUX_DA_6") (pintype "passive"))
    )
    (net (code "67") (name "unconnected-(U3-CLKOUT-Pad22)") (class "Default")
      (node (ref "U3") (pin "22") (pinfunction "CLKOUT_22") (pintype "passive"))
    )
    (net (code "68") (name "unconnected-(U3-Pad2)") (class "Default")
      (node (ref "U3") (pin "2") (pinfunction "2_2") (pintype "passive"))
    )
    (net (code "69") (name "unconnected-(U3-Pad3)") (class "Default")
      (node (ref "U3") (pin "3") (pinfunction "3_3") (pintype "passive"))
    )
    (net (code "70") (name "unconnected-(U3-Pad4)") (class "Default")
      (node (ref "U3") (pin "4") (pinfunction "4_4") (pintype "passive"))
    )
    (net (code "71") (name "unconnected-(U3-Pad5)") (class "Default")
      (node (ref "U3") (pin "5") (pinfunction "5_5") (pintype "passive"))
    )
    (net (code "72") (name "unconnected-(U3-Pad14)") (class "Default")
      (node (ref "U3") (pin "14") (pinfunction "14_14") (pintype "passive"))
    )
    (net (code "73") (name "unconnected-(U3-Pad15)") (class "Default")
      (node (ref "U3") (pin "15") (pinfunction "15_15") (pintype "passive"))
    )
    (net (code "74") (name "unconnected-(U3-Pad16)") (class "Default")
      (node (ref "U3") (pin "16") (pinfunction "16_16") (pintype "passive"))
    )
    (net (code "75") (name "unconnected-(U3-Pad17)") (class "Default")
      (node (ref "U3") (pin "17") (pinfunction "17_17") (pintype "passive"))
    )
    (net (code "76") (name "unconnected-(U3-RESV-Pad19)") (class "Default")
      (node (ref "U3") (pin "19") (pinfunction "RESV_19") (pintype "passive"))
    )
    (net (code "77") (name "unconnected-(U3-RESV-Pad21)") (class "Default")
      (node (ref "U3") (pin "21") (pinfunction "RESV_21") (pintype "passive"))
    )
  )
)
